# P3_CCD_CAM_BOARD_CAMERA.net
KiCad netlist of a schematic drawn in Altium Designer
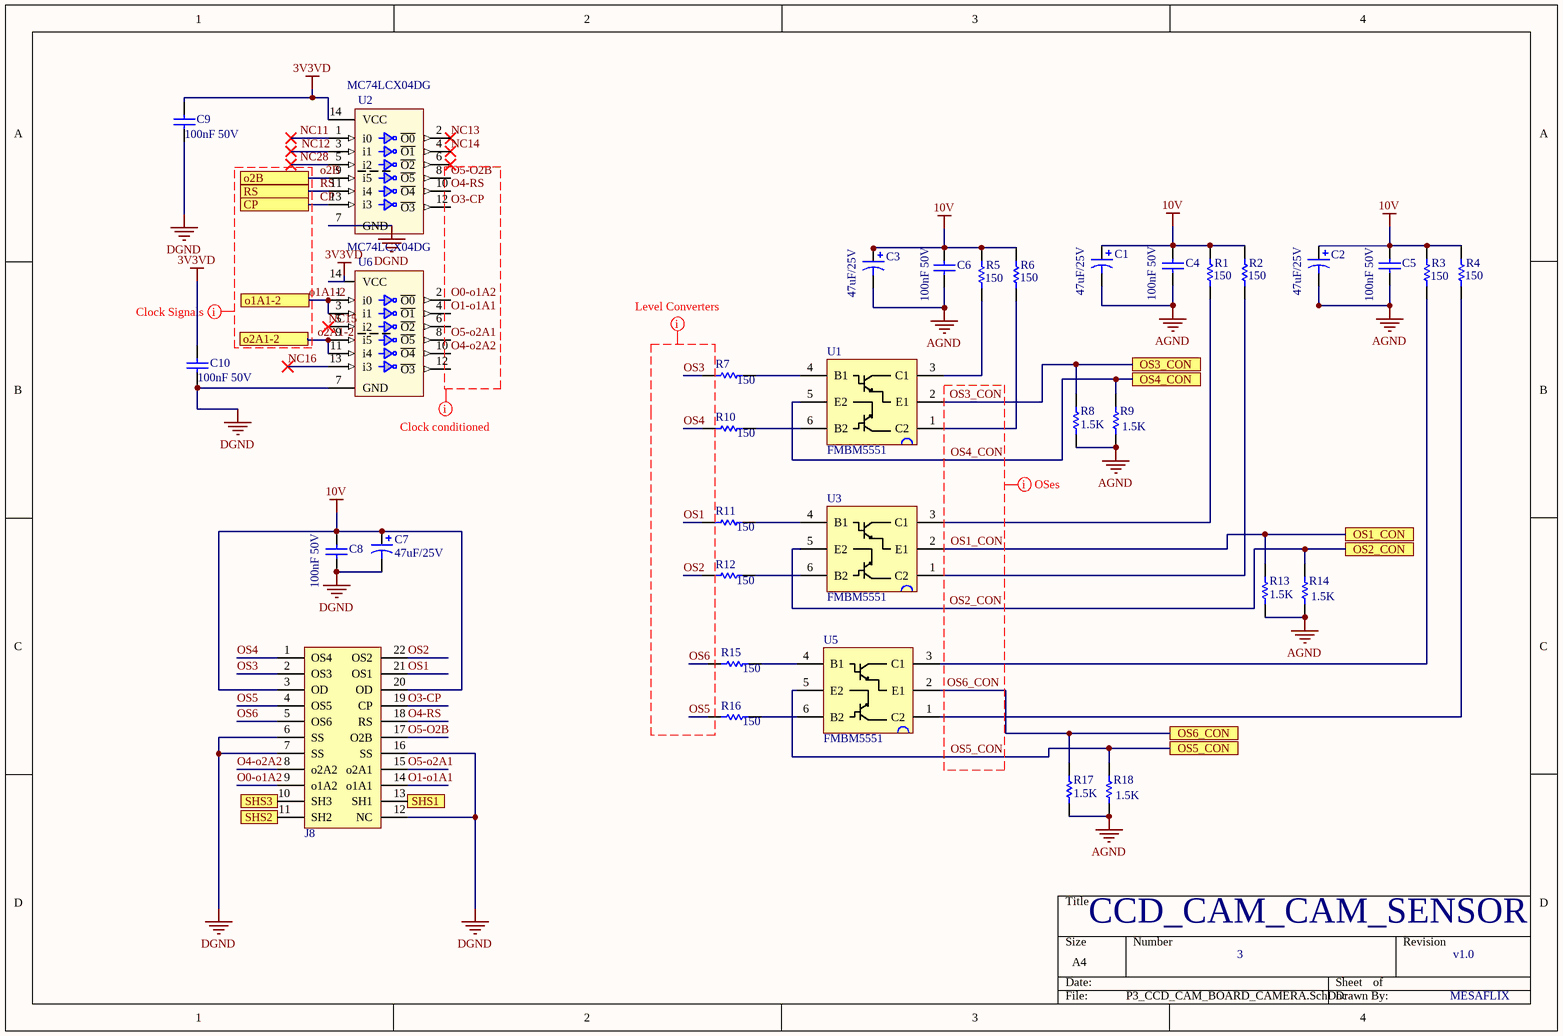
[diagram p0: P3_CCD_CAM_BOARD_CAMERA.SchDoc]

(export (version "E")
  (design (tool "Eeschema 10.0.6"))
  (components
    (comp (ref "C1")
      (value "47uF/25V")
      (footprint "1206 (3216)")
      (fields (field (name "MFR PART #") "GRM31CR61E476ME44L") (field (name "Comment") "Cap"))
      (libsource (lib "CCD_board") (part "Cap Chip Pol"))
    )
    (comp (ref "C2")
      (value "47uF/25V")
      (footprint "1206 (3216)")
      (fields (field (name "MFR PART #") "GRM31CR61E476ME44L") (field (name "Comment") "Cap"))
      (libsource (lib "CCD_board") (part "Cap Chip Pol"))
    )
    (comp (ref "C3")
      (value "47uF/25V")
      (footprint "1206 (3216)")
      (fields (field (name "MFR PART #") "GRM31CR61E476ME44L") (field (name "Comment") "Cap"))
      (libsource (lib "CCD_board") (part "Cap Chip Pol"))
    )
    (comp (ref "C4")
      (value "100nF 50V")
      (footprint "CAP0603")
      (description "CAP CER 0.1UF 50V X7R 0603")
      (libsource (lib "CAP_Library") (part "CAP0603_100nF"))
    )
    (comp (ref "C5")
      (value "100nF 50V")
      (footprint "CAP0603")
      (description "CAP CER 0.1UF 50V X7R 0603")
      (libsource (lib "CAP_Library") (part "CAP0603_100nF"))
    )
    (comp (ref "C6")
      (value "100nF 50V")
      (footprint "CAP0603")
      (description "CAP CER 0.1UF 50V X7R 0603")
      (libsource (lib "CAP_Library") (part "CAP0603_100nF"))
    )
    (comp (ref "C7")
      (value "47uF/25V")
      (footprint "1206 (3216)")
      (fields (field (name "MFR PART #") "GRM31CR61E476ME44L") (field (name "Comment") "Cap"))
      (libsource (lib "CCD_board") (part "Cap Chip Pol"))
    )
    (comp (ref "C8")
      (value "100nF 50V")
      (footprint "CAP0603")
      (description "CAP CER 0.1UF 50V X7R 0603")
      (libsource (lib "CAP_Library") (part "CAP0603_100nF"))
    )
    (comp (ref "C9")
      (value "100nF 50V")
      (footprint "CAP0603")
      (description "CAP CER 0.1UF 50V X7R 0603")
      (libsource (lib "CAP_Library") (part "CAP0603_100nF"))
    )
    (comp (ref "C10")
      (value "100nF 50V")
      (footprint "CAP0603")
      (description "CAP CER 0.1UF 50V X7R 0603")
      (libsource (lib "CAP_Library") (part "CAP0603_100nF"))
    )
    (comp (ref "J8")
      (value "CONN")
      (footprint "CCD_SENSOR_PIN")
      (description "11x2 Connector")
      (libsource (lib "CCD_CAM_BOARD") (part "CCD_SENSOR_PIN"))
    )
    (comp (ref "R1")
      (value "150")
      (footprint "0402 (1005)")
      (description "Semiconductor Resistor")
      (fields (field (name "MFR PART #") "RC0402FR-07150RL") (field (name "Comment") "Res Semi"))
      (libsource (lib "Miscellaneous Devices") (part "Res Semi"))
    )
    (comp (ref "R2")
      (value "150")
      (footprint "0402 (1005)")
      (description "Semiconductor Resistor")
      (fields (field (name "MFR PART #") "RC0402FR-07150RL") (field (name "Comment") "Res Semi"))
      (libsource (lib "Miscellaneous Devices") (part "Res Semi"))
    )
    (comp (ref "R3")
      (value "150")
      (footprint "0402 (1005)")
      (description "Semiconductor Resistor")
      (fields (field (name "MFR PART #") "RC0402FR-07150RL") (field (name "Comment") "Res Semi"))
      (libsource (lib "Miscellaneous Devices") (part "Res Semi"))
    )
    (comp (ref "R4")
      (value "150")
      (footprint "0402 (1005)")
      (description "Semiconductor Resistor")
      (fields (field (name "MFR PART #") "RC0402FR-07150RL") (field (name "Comment") "Res Semi"))
      (libsource (lib "Miscellaneous Devices") (part "Res Semi"))
    )
    (comp (ref "R5")
      (value "150")
      (footprint "0402 (1005)")
      (description "Semiconductor Resistor")
      (fields (field (name "MFR PART #") "RC0402FR-07150RL") (field (name "Comment") "Res Semi"))
      (libsource (lib "Miscellaneous Devices") (part "Res Semi"))
    )
    (comp (ref "R6")
      (value "150")
      (footprint "0402 (1005)")
      (description "Semiconductor Resistor")
      (fields (field (name "MFR PART #") "RC0402FR-07150RL") (field (name "Comment") "Res Semi"))
      (libsource (lib "Miscellaneous Devices") (part "Res Semi"))
    )
    (comp (ref "R7")
      (value "150")
      (footprint "0402 (1005)")
      (description "Semiconductor Resistor")
      (fields (field (name "MFR PART #") "RC0402FR-07150RL") (field (name "Comment") "Res Semi"))
      (libsource (lib "Miscellaneous Devices") (part "Res Semi"))
    )
    (comp (ref "R8")
      (value "1.5K")
      (footprint "0402 (1005)")
      (description "Semiconductor Resistor")
      (fields (field (name "MFR PART #") "RC0402FR-071K5L") (field (name "Comment") "Res Semi"))
      (libsource (lib "Miscellaneous Devices") (part "Res Semi"))
    )
    (comp (ref "R9")
      (value "1.5K")
      (footprint "0402 (1005)")
      (description "Semiconductor Resistor")
      (fields (field (name "MFR PART #") "RC0402FR-071K5L") (field (name "Comment") "Res Semi"))
      (libsource (lib "Miscellaneous Devices") (part "Res Semi"))
    )
    (comp (ref "R10")
      (value "150")
      (footprint "0402 (1005)")
      (description "Semiconductor Resistor")
      (fields (field (name "MFR PART #") "RC0402FR-07150RL") (field (name "Comment") "Res Semi"))
      (libsource (lib "Miscellaneous Devices") (part "Res Semi"))
    )
    (comp (ref "R11")
      (value "150")
      (footprint "0402 (1005)")
      (description "Semiconductor Resistor")
      (fields (field (name "MFR PART #") "RC0402FR-07150RL") (field (name "Comment") "Res Semi"))
      (libsource (lib "Miscellaneous Devices") (part "Res Semi"))
    )
    (comp (ref "R12")
      (value "150")
      (footprint "0402 (1005)")
      (description "Semiconductor Resistor")
      (fields (field (name "MFR PART #") "RC0402FR-07150RL") (field (name "Comment") "Res Semi"))
      (libsource (lib "Miscellaneous Devices") (part "Res Semi"))
    )
    (comp (ref "R13")
      (value "1.5K")
      (footprint "0402 (1005)")
      (description "Semiconductor Resistor")
      (fields (field (name "MFR PART #") "RC0402FR-071K5L") (field (name "Comment") "Res Semi"))
      (libsource (lib "Miscellaneous Devices") (part "Res Semi"))
    )
    (comp (ref "R14")
      (value "1.5K")
      (footprint "0402 (1005)")
      (description "Semiconductor Resistor")
      (fields (field (name "MFR PART #") "RC0402FR-071K5L") (field (name "Comment") "Res Semi"))
      (libsource (lib "Miscellaneous Devices") (part "Res Semi"))
    )
    (comp (ref "R15")
      (value "150")
      (footprint "0402 (1005)")
      (description "Semiconductor Resistor")
      (fields (field (name "MFR PART #") "RC0402FR-07150RL") (field (name "Comment") "Res Semi"))
      (libsource (lib "Miscellaneous Devices") (part "Res Semi"))
    )
    (comp (ref "R16")
      (value "150")
      (footprint "0402 (1005)")
      (description "Semiconductor Resistor")
      (fields (field (name "MFR PART #") "RC0402FR-07150RL") (field (name "Comment") "Res Semi"))
      (libsource (lib "Miscellaneous Devices") (part "Res Semi"))
    )
    (comp (ref "R17")
      (value "1.5K")
      (footprint "0402 (1005)")
      (description "Semiconductor Resistor")
      (fields (field (name "MFR PART #") "RC0402FR-071K5L") (field (name "Comment") "Res Semi"))
      (libsource (lib "Miscellaneous Devices") (part "Res Semi"))
    )
    (comp (ref "R18")
      (value "1.5K")
      (footprint "0402 (1005)")
      (description "Semiconductor Resistor")
      (fields (field (name "MFR PART #") "RC0402FR-071K5L") (field (name "Comment") "Res Semi"))
      (libsource (lib "Miscellaneous Devices") (part "Res Semi"))
    )
    (comp (ref "U1")
      (value "FMBM5551")
      (footprint "SOT95P285X140-6N")
      (libsource (lib "CCD_board") (part "FMBM5551"))
    )
    (comp (ref "U2")
      (value "MC74LCX04DG")
      (footprint "SOIC127P600X175-14N")
      (description "Inverter IC 6 Channel 14-SOIC")
      (libsource (lib "CCD_board") (part "MC74LCX04DG"))
    )
    (comp (ref "U3")
      (value "FMBM5551")
      (footprint "SOT95P285X140-6N")
      (libsource (lib "CCD_board") (part "FMBM5551"))
    )
    (comp (ref "U5")
      (value "FMBM5551")
      (footprint "SOT95P285X140-6N")
      (libsource (lib "CCD_board") (part "FMBM5551"))
    )
    (comp (ref "U6")
      (value "MC74LCX04DG")
      (footprint "SOIC127P600X175-14N")
      (description "Inverter IC 6 Channel 14-SOIC")
      (libsource (lib "CCD_board") (part "MC74LCX04DG"))
    )
  )
  (nets
    (net (code "1") (name "/CP") (class "Default")
      (node (ref "U2") (pin "13") (pinfunction "i3_13") (pintype "input"))
    )
    (net (code "2") (name "/NC11") (class "Default")
      (node (ref "U2") (pin "1") (pinfunction "i0_1") (pintype "input+no_connect"))
    )
    (net (code "3") (name "/NC12") (class "Default")
      (node (ref "U2") (pin "3") (pinfunction "i1_3") (pintype "input+no_connect"))
    )
    (net (code "4") (name "/NC13") (class "Default")
      (node (ref "U2") (pin "2") (pinfunction "~{O0}_2") (pintype "output+no_connect"))
    )
    (net (code "5") (name "/NC14") (class "Default")
      (node (ref "U2") (pin "4") (pinfunction "~{O1}_4") (pintype "output+no_connect"))
    )
    (net (code "6") (name "/NC15") (class "Default")
      (node (ref "U6") (pin "5") (pinfunction "i2_5") (pintype "input+no_connect"))
    )
    (net (code "7") (name "/NC16") (class "Default")
      (node (ref "U6") (pin "13") (pinfunction "i3_13") (pintype "input+no_connect"))
    )
    (net (code "8") (name "/NC28") (class "Default")
      (node (ref "U2") (pin "5") (pinfunction "i2_5") (pintype "input+no_connect"))
    )
    (net (code "9") (name "/O0-o1A2") (class "Default")
      (node (ref "J8") (pin "9") (pinfunction "o1A2_9") (pintype "passive"))
      (node (ref "U6") (pin "2") (pinfunction "~{O0}_2") (pintype "output"))
    )
    (net (code "10") (name "/O1-o1A1") (class "Default")
      (node (ref "J8") (pin "14") (pinfunction "o1A1_14") (pintype "passive"))
      (node (ref "U6") (pin "4") (pinfunction "~{O1}_4") (pintype "output"))
    )
    (net (code "11") (name "/O3-CP") (class "Default")
      (node (ref "J8") (pin "19") (pinfunction "CP_19") (pintype "passive"))
      (node (ref "U2") (pin "12") (pinfunction "~{O3}_12") (pintype "output"))
    )
    (net (code "12") (name "/O4-RS") (class "Default")
      (node (ref "J8") (pin "18") (pinfunction "RS_18") (pintype "passive"))
      (node (ref "U2") (pin "10") (pinfunction "~{O4}_10") (pintype "output"))
    )
    (net (code "13") (name "/O4-o2A2") (class "Default")
      (node (ref "J8") (pin "8") (pinfunction "o2A2_8") (pintype "passive"))
      (node (ref "U6") (pin "10") (pinfunction "~{O4}_10") (pintype "output"))
    )
    (net (code "14") (name "/O5-O2B") (class "Default")
      (node (ref "J8") (pin "17") (pinfunction "O2B_17") (pintype "passive"))
      (node (ref "U2") (pin "8") (pinfunction "~{O5}_8") (pintype "output"))
    )
    (net (code "15") (name "/O5-o2A1") (class "Default")
      (node (ref "J8") (pin "15") (pinfunction "o2A1_15") (pintype "passive"))
      (node (ref "U6") (pin "8") (pinfunction "~{O5}_8") (pintype "output"))
    )
    (net (code "16") (name "/OS1") (class "Default")
      (node (ref "J8") (pin "21") (pinfunction "OS1_21") (pintype "passive"))
      (node (ref "R11") (pin "1") (pinfunction "1_1") (pintype "passive"))
    )
    (net (code "17") (name "/OS1_CON") (class "Default")
      (node (ref "R13") (pin "1") (pinfunction "1_1") (pintype "passive"))
      (node (ref "U3") (pin "2") (pinfunction "E1_2") (pintype "passive"))
    )
    (net (code "18") (name "/OS2") (class "Default")
      (node (ref "J8") (pin "22") (pinfunction "OS2_22") (pintype "passive"))
      (node (ref "R12") (pin "1") (pinfunction "1_1") (pintype "passive"))
    )
    (net (code "19") (name "/OS2_CON") (class "Default")
      (node (ref "R14") (pin "2") (pinfunction "2_2") (pintype "passive"))
      (node (ref "U3") (pin "5") (pinfunction "E2_5") (pintype "passive"))
    )
    (net (code "20") (name "/OS3") (class "Default")
      (node (ref "J8") (pin "2") (pinfunction "OS3_2") (pintype "passive"))
      (node (ref "R7") (pin "1") (pinfunction "1_1") (pintype "passive"))
    )
    (net (code "21") (name "/OS3_CON") (class "Default")
      (node (ref "R8") (pin "1") (pinfunction "1_1") (pintype "passive"))
      (node (ref "U1") (pin "2") (pinfunction "E1_2") (pintype "passive"))
    )
    (net (code "22") (name "/OS4") (class "Default")
      (node (ref "J8") (pin "1") (pinfunction "OS4_1") (pintype "passive"))
      (node (ref "R10") (pin "1") (pinfunction "1_1") (pintype "passive"))
    )
    (net (code "23") (name "/OS4_CON") (class "Default")
      (node (ref "R9") (pin "2") (pinfunction "2_2") (pintype "passive"))
      (node (ref "U1") (pin "5") (pinfunction "E2_5") (pintype "passive"))
    )
    (net (code "24") (name "/OS5") (class "Default")
      (node (ref "J8") (pin "4") (pinfunction "OS5_4") (pintype "passive"))
      (node (ref "R16") (pin "1") (pinfunction "1_1") (pintype "passive"))
    )
    (net (code "25") (name "/OS5_CON") (class "Default")
      (node (ref "R18") (pin "2") (pinfunction "2_2") (pintype "passive"))
      (node (ref "U5") (pin "5") (pinfunction "E2_5") (pintype "passive"))
    )
    (net (code "26") (name "/OS6") (class "Default")
      (node (ref "J8") (pin "5") (pinfunction "OS6_5") (pintype "passive"))
      (node (ref "R15") (pin "1") (pinfunction "1_1") (pintype "passive"))
    )
    (net (code "27") (name "/OS6_CON") (class "Default")
      (node (ref "R17") (pin "1") (pinfunction "1_1") (pintype "passive"))
      (node (ref "U5") (pin "2") (pinfunction "E1_2") (pintype "passive"))
    )
    (net (code "28") (name "/RS") (class "Default")
      (node (ref "U2") (pin "11") (pinfunction "i4_11") (pintype "input"))
    )
    (net (code "29") (name "/SHS1") (class "Default")
      (node (ref "J8") (pin "13") (pinfunction "SH1_13") (pintype "passive"))
    )
    (net (code "30") (name "/SHS2") (class "Default")
      (node (ref "J8") (pin "11") (pinfunction "SH2_11") (pintype "passive"))
    )
    (net (code "31") (name "/SHS3") (class "Default")
      (node (ref "J8") (pin "10") (pinfunction "SH3_10") (pintype "passive"))
    )
    (net (code "32") (name "/o1A1-2") (class "Default")
      (node (ref "U6") (pin "1") (pinfunction "i0_1") (pintype "input"))
      (node (ref "U6") (pin "3") (pinfunction "i1_3") (pintype "input"))
    )
    (net (code "33") (name "/o2A1-2") (class "Default")
      (node (ref "U6") (pin "11") (pinfunction "i4_11") (pintype "input"))
      (node (ref "U6") (pin "9") (pinfunction "i5_9") (pintype "input"))
    )
    (net (code "34") (name "/o2B") (class "Default")
      (node (ref "U2") (pin "9") (pinfunction "i5_9") (pintype "input"))
    )
    (net (code "35") (name "3V3VD") (class "Default")
      (node (ref "C10") (pin "2") (pinfunction "2_2") (pintype "passive"))
      (node (ref "C9") (pin "2") (pinfunction "2_2") (pintype "passive"))
      (node (ref "U2") (pin "14") (pinfunction "VCC_14") (pintype "power_in"))
      (node (ref "U6") (pin "14") (pinfunction "VCC_14") (pintype "power_in"))
    )
    (net (code "36") (name "10V") (class "Default")
      (node (ref "C1") (pin "1") (pinfunction "1_1") (pintype "passive"))
      (node (ref "C2") (pin "1") (pinfunction "1_1") (pintype "passive"))
      (node (ref "C3") (pin "1") (pinfunction "1_1") (pintype "passive"))
      (node (ref "C4") (pin "2") (pinfunction "2_2") (pintype "passive"))
      (node (ref "C5") (pin "2") (pinfunction "2_2") (pintype "passive"))
      (node (ref "C6") (pin "2") (pinfunction "2_2") (pintype "passive"))
      (node (ref "C7") (pin "1") (pinfunction "1_1") (pintype "passive"))
      (node (ref "C8") (pin "2") (pinfunction "2_2") (pintype "passive"))
      (node (ref "J8") (pin "20") (pinfunction "OD_20") (pintype "passive"))
      (node (ref "J8") (pin "3") (pinfunction "OD_3") (pintype "passive"))
      (node (ref "R1") (pin "1") (pinfunction "1_1") (pintype "passive"))
      (node (ref "R2") (pin "1") (pinfunction "1_1") (pintype "passive"))
      (node (ref "R3") (pin "1") (pinfunction "1_1") (pintype "passive"))
      (node (ref "R4") (pin "1") (pinfunction "1_1") (pintype "passive"))
      (node (ref "R5") (pin "1") (pinfunction "1_1") (pintype "passive"))
      (node (ref "R6") (pin "1") (pinfunction "1_1") (pintype "passive"))
    )
    (net (code "37") (name "AGND") (class "Default")
      (node (ref "C1") (pin "2") (pinfunction "2_2") (pintype "passive"))
      (node (ref "C2") (pin "2") (pinfunction "2_2") (pintype "passive"))
      (node (ref "C3") (pin "2") (pinfunction "2_2") (pintype "passive"))
      (node (ref "C4") (pin "1") (pinfunction "1_1") (pintype "passive"))
      (node (ref "C5") (pin "1") (pinfunction "1_1") (pintype "passive"))
      (node (ref "C6") (pin "1") (pinfunction "1_1") (pintype "passive"))
      (node (ref "R13") (pin "2") (pinfunction "2_2") (pintype "passive"))
      (node (ref "R14") (pin "1") (pinfunction "1_1") (pintype "passive"))
      (node (ref "R17") (pin "2") (pinfunction "2_2") (pintype "passive"))
      (node (ref "R18") (pin "1") (pinfunction "1_1") (pintype "passive"))
      (node (ref "R8") (pin "2") (pinfunction "2_2") (pintype "passive"))
      (node (ref "R9") (pin "1") (pinfunction "1_1") (pintype "passive"))
    )
    (net (code "38") (name "DGND") (class "Default")
      (node (ref "C10") (pin "1") (pinfunction "1_1") (pintype "passive"))
      (node (ref "C7") (pin "2") (pinfunction "2_2") (pintype "passive"))
      (node (ref "C8") (pin "1") (pinfunction "1_1") (pintype "passive"))
      (node (ref "C9") (pin "1") (pinfunction "1_1") (pintype "passive"))
      (node (ref "J8") (pin "12") (pinfunction "NC_12") (pintype "passive"))
      (node (ref "J8") (pin "16") (pinfunction "SS_16") (pintype "passive"))
      (node (ref "J8") (pin "6") (pinfunction "SS_6") (pintype "passive"))
      (node (ref "J8") (pin "7") (pinfunction "SS_7") (pintype "passive"))
      (node (ref "U2") (pin "7") (pinfunction "GND_7") (pintype "passive"))
      (node (ref "U6") (pin "7") (pinfunction "GND_7") (pintype "passive"))
    )
    (net (code "39") (name "Net-(U1-B1)") (class "Default")
      (node (ref "R7") (pin "2") (pinfunction "2_2") (pintype "passive"))
      (node (ref "U1") (pin "4") (pinfunction "B1_4") (pintype "passive"))
    )
    (net (code "40") (name "Net-(U1-B2)") (class "Default")
      (node (ref "R10") (pin "2") (pinfunction "2_2") (pintype "passive"))
      (node (ref "U1") (pin "6") (pinfunction "B2_6") (pintype "passive"))
    )
    (net (code "41") (name "Net-(U1-C1)") (class "Default")
      (node (ref "R5") (pin "2") (pinfunction "2_2") (pintype "passive"))
      (node (ref "U1") (pin "3") (pinfunction "C1_3") (pintype "passive"))
    )
    (net (code "42") (name "Net-(U1-C2)") (class "Default")
      (node (ref "R6") (pin "2") (pinfunction "2_2") (pintype "passive"))
      (node (ref "U1") (pin "1") (pinfunction "C2_1") (pintype "passive"))
    )
    (net (code "43") (name "Net-(U3-B1)") (class "Default")
      (node (ref "R11") (pin "2") (pinfunction "2_2") (pintype "passive"))
      (node (ref "U3") (pin "4") (pinfunction "B1_4") (pintype "passive"))
    )
    (net (code "44") (name "Net-(U3-B2)") (class "Default")
      (node (ref "R12") (pin "2") (pinfunction "2_2") (pintype "passive"))
      (node (ref "U3") (pin "6") (pinfunction "B2_6") (pintype "passive"))
    )
    (net (code "45") (name "Net-(U3-C1)") (class "Default")
      (node (ref "R1") (pin "2") (pinfunction "2_2") (pintype "passive"))
      (node (ref "U3") (pin "3") (pinfunction "C1_3") (pintype "passive"))
    )
    (net (code "46") (name "Net-(U3-C2)") (class "Default")
      (node (ref "R2") (pin "2") (pinfunction "2_2") (pintype "passive"))
      (node (ref "U3") (pin "1") (pinfunction "C2_1") (pintype "passive"))
    )
    (net (code "47") (name "Net-(U5-B1)") (class "Default")
      (node (ref "R15") (pin "2") (pinfunction "2_2") (pintype "passive"))
      (node (ref "U5") (pin "4") (pinfunction "B1_4") (pintype "passive"))
    )
    (net (code "48") (name "Net-(U5-B2)") (class "Default")
      (node (ref "R16") (pin "2") (pinfunction "2_2") (pintype "passive"))
      (node (ref "U5") (pin "6") (pinfunction "B2_6") (pintype "passive"))
    )
    (net (code "49") (name "Net-(U5-C1)") (class "Default")
      (node (ref "R3") (pin "2") (pinfunction "2_2") (pintype "passive"))
      (node (ref "U5") (pin "3") (pinfunction "C1_3") (pintype "passive"))
    )
    (net (code "50") (name "Net-(U5-C2)") (class "Default")
      (node (ref "R4") (pin "2") (pinfunction "2_2") (pintype "passive"))
      (node (ref "U5") (pin "1") (pinfunction "C2_1") (pintype "passive"))
    )
    (net (code "51") (name "unconnected-(U2-~{O2}-Pad6)") (class "Default")
      (node (ref "U2") (pin "6") (pinfunction "~{O2}_6") (pintype "output+no_connect"))
    )
    (net (code "52") (name "unconnected-(U6-~{O2}-Pad6)") (class "Default")
      (node (ref "U6") (pin "6") (pinfunction "~{O2}_6") (pintype "output"))
    )
    (net (code "53") (name "unconnected-(U6-~{O3}-Pad12)") (class "Default")
      (node (ref "U6") (pin "12") (pinfunction "~{O3}_12") (pintype "output"))
    )
  )
)
